# InkTime.net
KiCad netlist of a schematic drawn in EAGLE
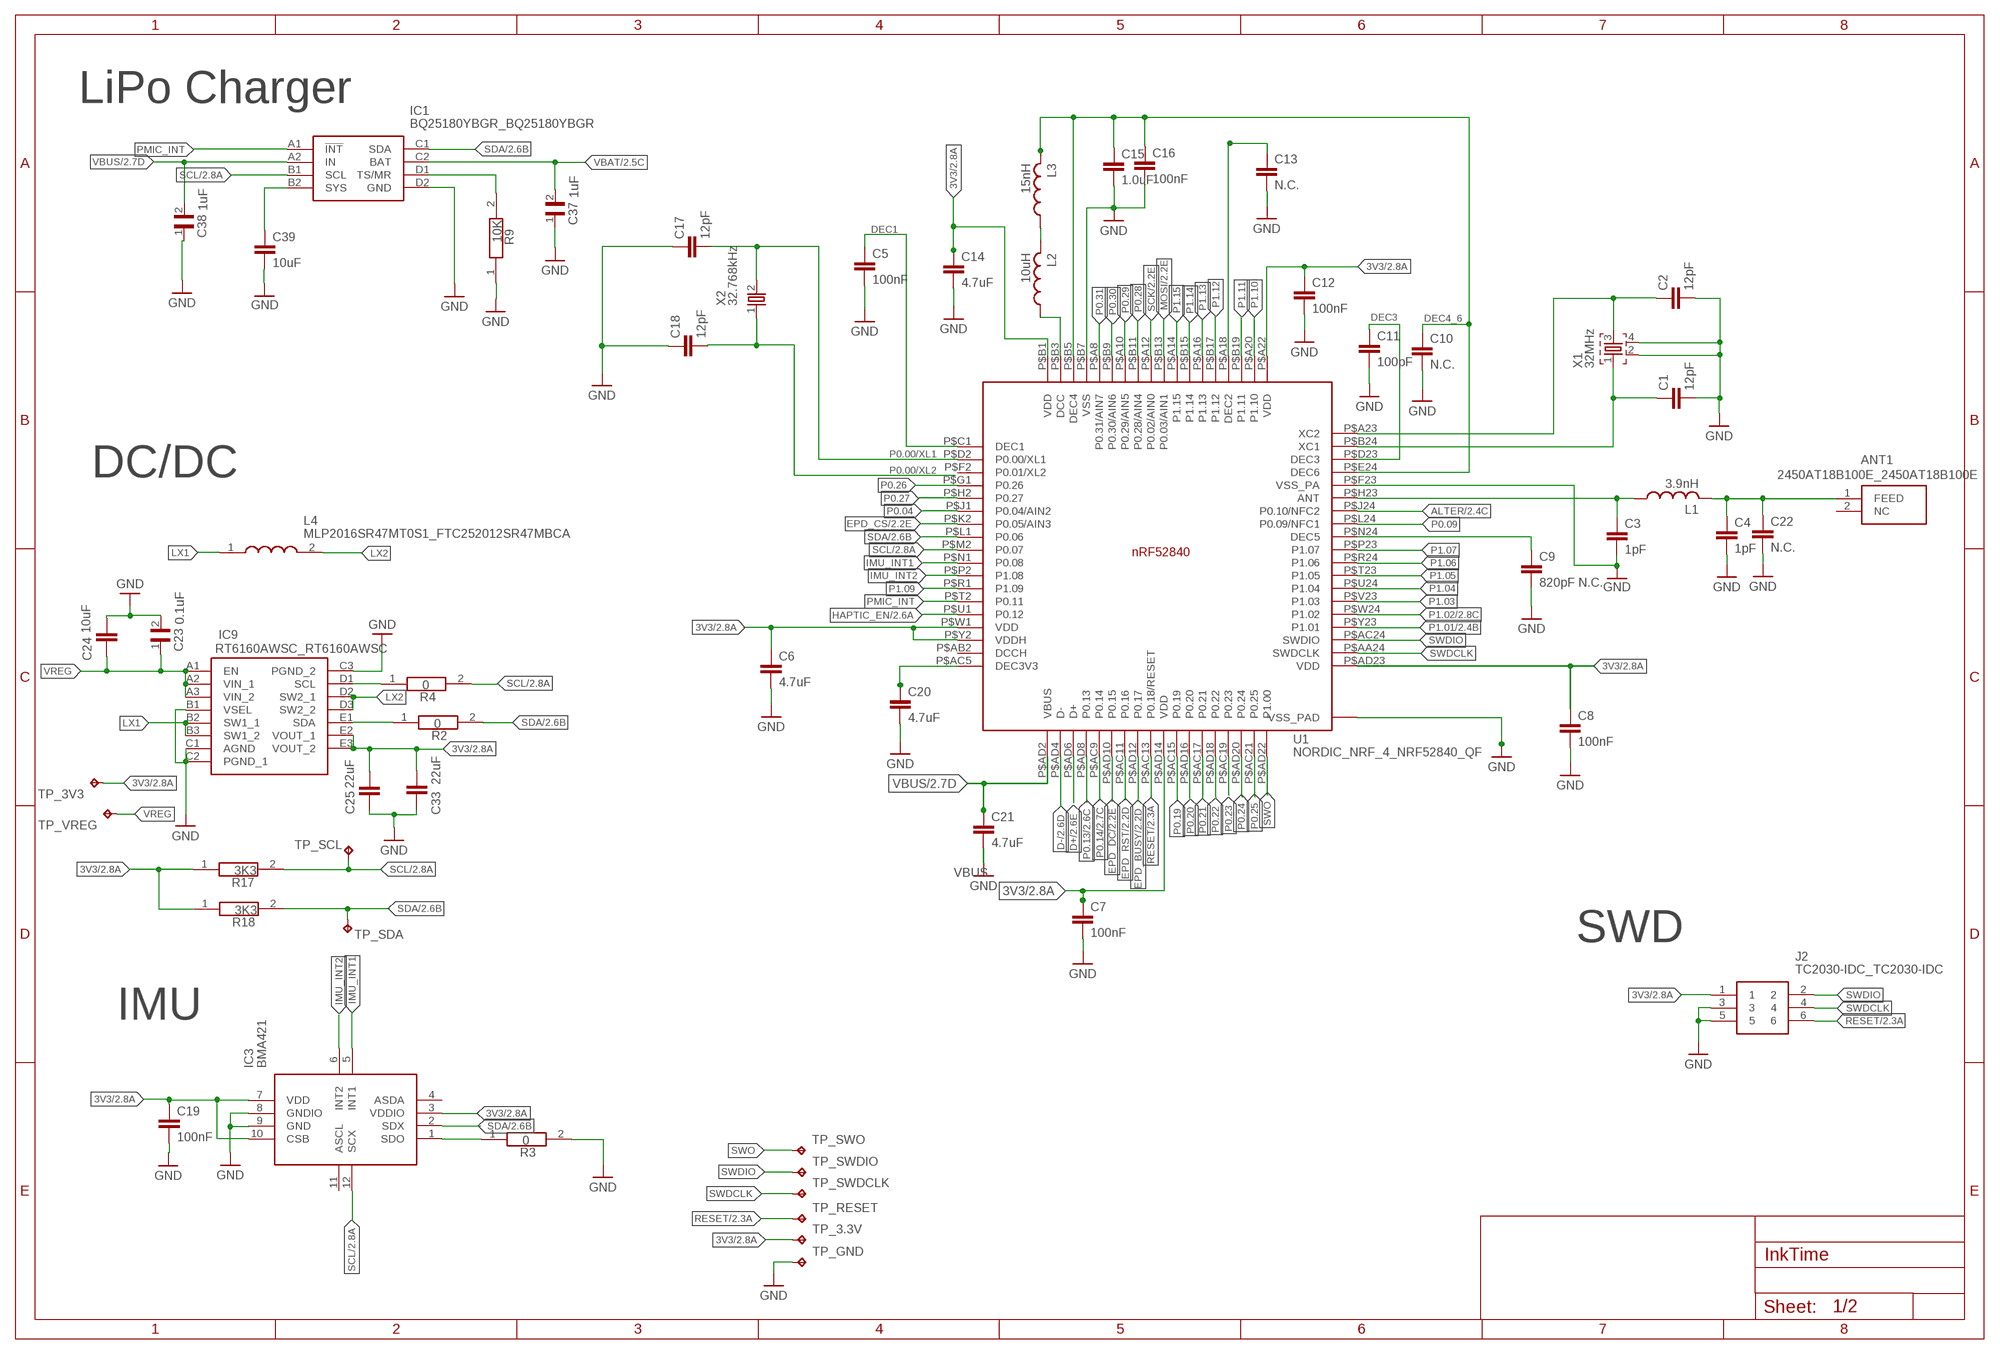
[diagram p0: schematic, sheet 1]
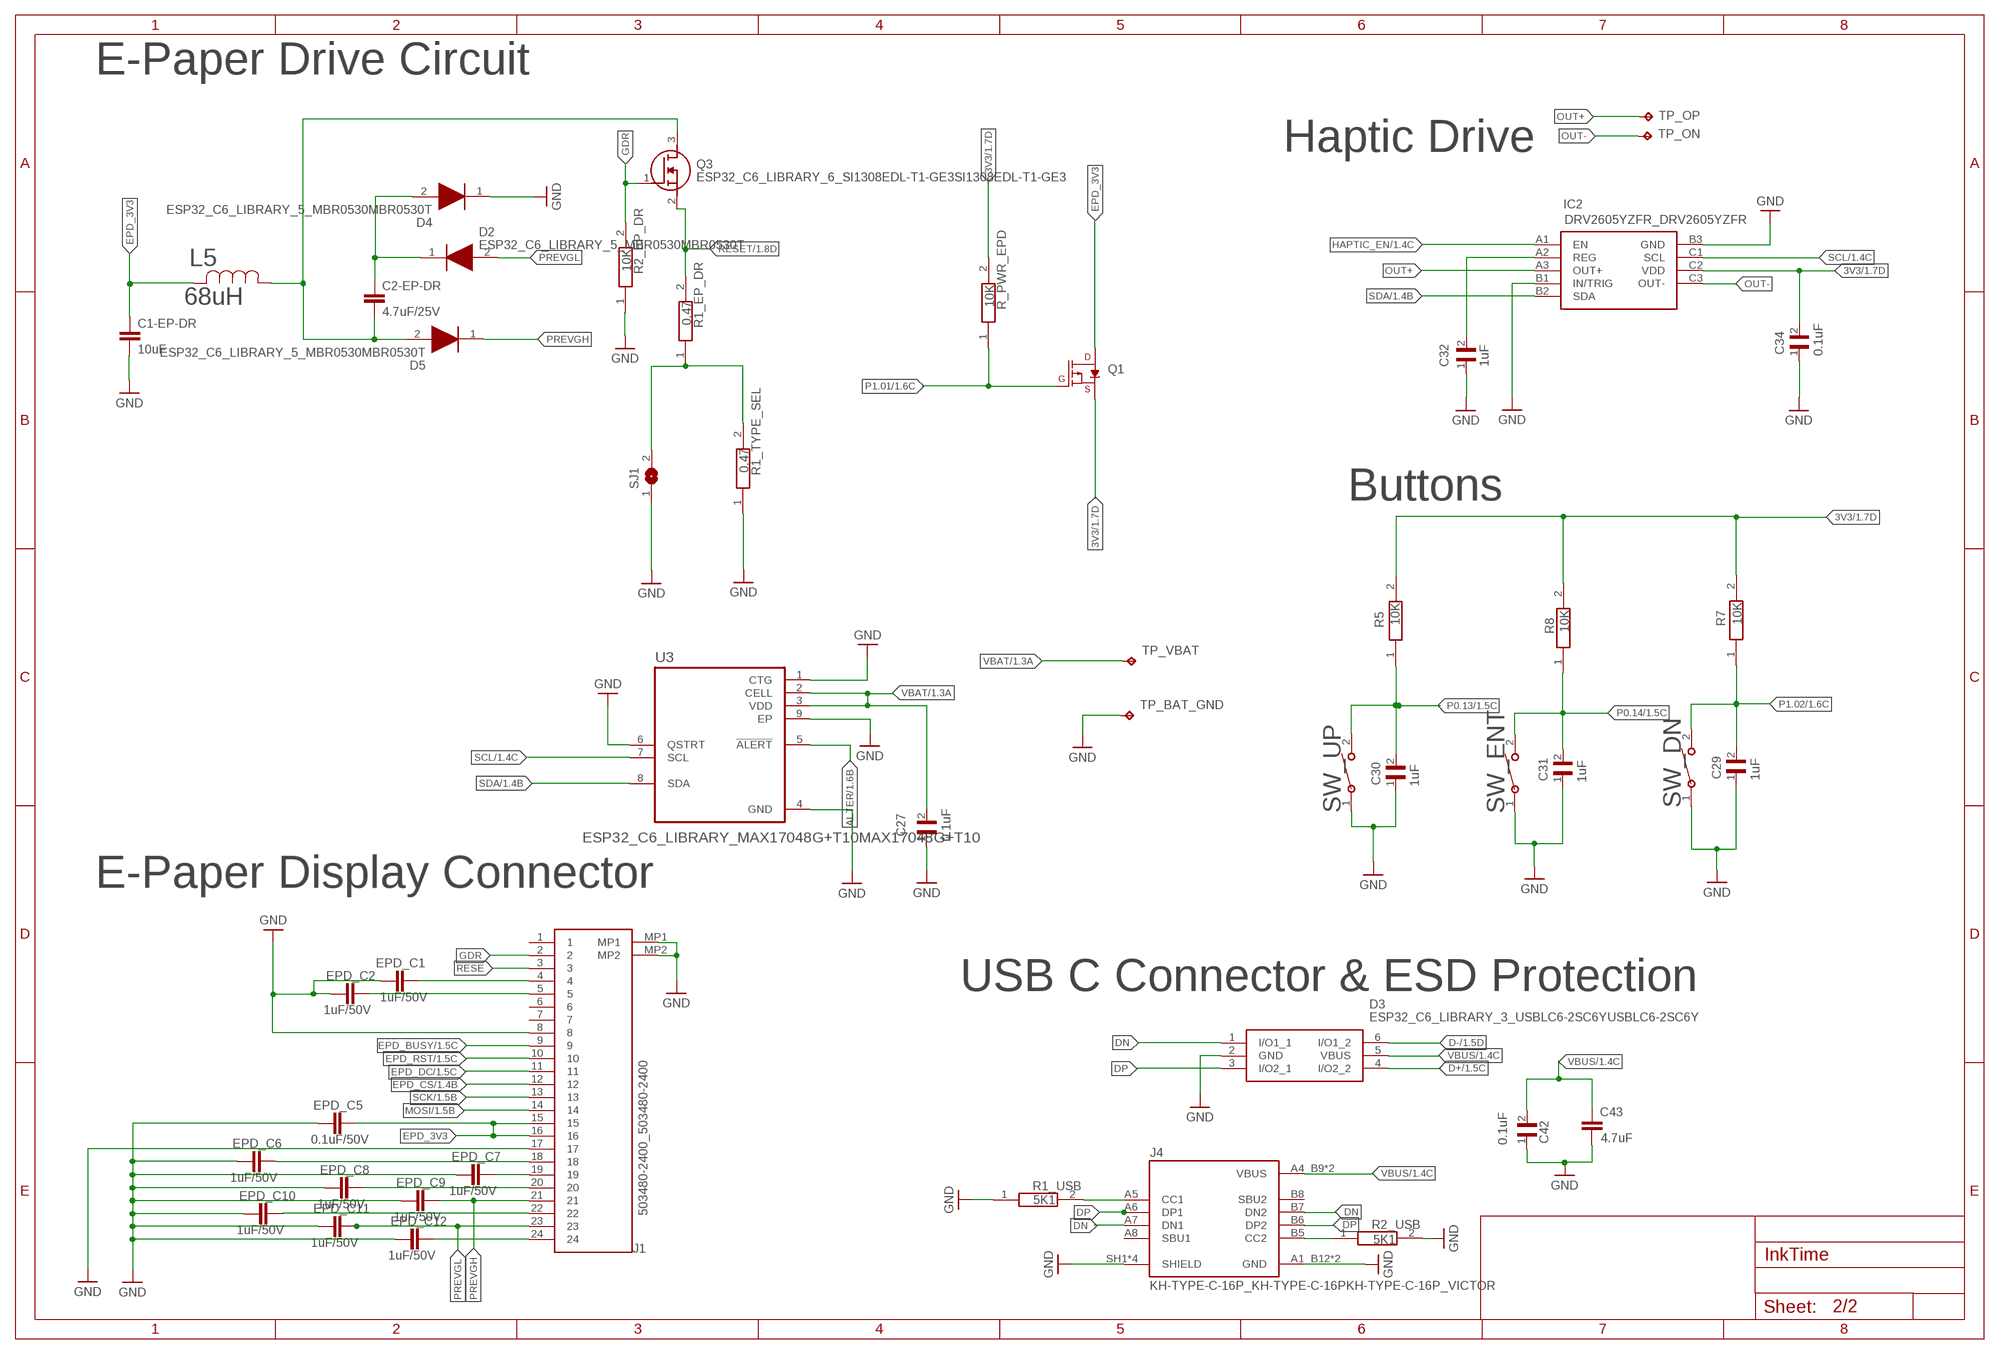
[diagram p1: schematic, sheet 2]

(export (version "E")
  (design (tool "Eeschema 10.0.6"))
  (components
    (comp (ref "ANT1")
      (value "2450AT18B100E_2450AT18B100E")
      (footprint "eagle-import:2450AT18B100E_ANTC3216X140N")
      (fields
        (field (name "ARROW_PART_NUMBER") "2450AT18B100E")
        (field (name "MOUSER_PART_NUMBER") "609-2450AT18B100E")
      )
      (libsource (lib "eagle-import") (part "2450AT18B100E_2450AT18B100E"))
    )
    (comp (ref "C1")
      (value "12pF")
      (footprint "eagle-import:NORDIC_NRF_3_RESC0201_N")
      (libsource (lib "eagle-import") (part "NORDIC_NRF_3_CAPACITOR_0201_N"))
    )
    (comp (ref "C2")
      (value "12pF")
      (footprint "eagle-import:NORDIC_NRF_3_RESC0201_N")
      (libsource (lib "eagle-import") (part "NORDIC_NRF_3_CAPACITOR_0201_N"))
    )
    (comp (ref "C3")
      (value "1pF")
      (footprint "eagle-import:NORDIC_NRF_3_RESC0201_N")
      (libsource (lib "eagle-import") (part "NORDIC_NRF_3_CAPACITOR_0201_N"))
    )
    (comp (ref "C4")
      (value "1pF")
      (footprint "eagle-import:NORDIC_NRF_3_RESC0201_N")
      (libsource (lib "eagle-import") (part "NORDIC_NRF_3_CAPACITOR_0201_N"))
    )
    (comp (ref "C5")
      (value "100nF")
      (footprint "eagle-import:NORDIC_NRF_3_RESC0201_N")
      (libsource (lib "eagle-import") (part "NORDIC_NRF_3_CAPACITOR_0201_N"))
    )
    (comp (ref "C6")
      (value "4.7uF")
      (footprint "eagle-import:NORDIC_NRF_3_RESC0402_N")
      (libsource (lib "eagle-import") (part "NORDIC_NRF_3_CAPACITORCAPACITOR_4020"))
    )
    (comp (ref "C7")
      (value "100nF")
      (footprint "eagle-import:NORDIC_NRF_3_RESC0201_N")
      (libsource (lib "eagle-import") (part "NORDIC_NRF_3_CAPACITOR_0201_N"))
    )
    (comp (ref "C8")
      (value "100nF")
      (footprint "eagle-import:NORDIC_NRF_3_RESC0201_N")
      (libsource (lib "eagle-import") (part "NORDIC_NRF_3_CAPACITOR_0201_N"))
    )
    (comp (ref "C9")
      (value "820pF N.C.")
      (footprint "eagle-import:NORDIC_NRF_3_RESC0201_N")
      (libsource (lib "eagle-import") (part "NORDIC_NRF_3_CAPACITOR_0201_N"))
    )
    (comp (ref "C10")
      (value "N.C.")
      (footprint "eagle-import:NORDIC_NRF_3_RESC0402_N")
      (libsource (lib "eagle-import") (part "NORDIC_NRF_3_CAPACITORCAPACITOR_4020"))
    )
    (comp (ref "C11")
      (value "100pF")
      (footprint "eagle-import:NORDIC_NRF_3_RESC0201_N")
      (libsource (lib "eagle-import") (part "NORDIC_NRF_3_CAPACITOR_0201_N"))
    )
    (comp (ref "C12")
      (value "100nF")
      (footprint "eagle-import:NORDIC_NRF_3_RESC0201_N")
      (libsource (lib "eagle-import") (part "NORDIC_NRF_3_CAPACITOR_0201_N"))
    )
    (comp (ref "C13")
      (value "N.C.")
      (footprint "eagle-import:NORDIC_NRF_3_RESC0201_N")
      (libsource (lib "eagle-import") (part "NORDIC_NRF_3_CAPACITOR_0201_N"))
    )
    (comp (ref "C14")
      (value "4.7uF")
      (footprint "eagle-import:NORDIC_NRF_3_RESC0402_N")
      (libsource (lib "eagle-import") (part "NORDIC_NRF_3_CAPACITORCAPACITOR_4020"))
    )
    (comp (ref "C15")
      (value "1.0uF")
      (footprint "eagle-import:NORDIC_NRF_3_RESC0402_N")
      (libsource (lib "eagle-import") (part "NORDIC_NRF_3_CAPACITORCAPACITOR_4020"))
    )
    (comp (ref "C16")
      (value "100nF")
      (footprint "eagle-import:NORDIC_NRF_3_RESC0201_N")
      (libsource (lib "eagle-import") (part "NORDIC_NRF_3_CAPACITOR_0201_N"))
    )
    (comp (ref "C17")
      (value "12pF")
      (footprint "eagle-import:NORDIC_NRF_3_RESC0201_N")
      (libsource (lib "eagle-import") (part "NORDIC_NRF_3_CAPACITOR_0201_N"))
    )
    (comp (ref "C18")
      (value "12pF")
      (footprint "eagle-import:NORDIC_NRF_3_RESC0201_N")
      (libsource (lib "eagle-import") (part "NORDIC_NRF_3_CAPACITOR_0201_N"))
    )
    (comp (ref "C19")
      (value "100nF")
      (footprint "eagle-import:NORDIC_NRF_3_RESC0201_N")
      (libsource (lib "eagle-import") (part "NORDIC_NRF_3_CAPACITOR_0201_N"))
    )
    (comp (ref "C20")
      (value "4.7uF")
      (footprint "eagle-import:NORDIC_NRF_3_RESC0402_N")
      (libsource (lib "eagle-import") (part "NORDIC_NRF_3_CAPACITORCAPACITOR_4020"))
    )
    (comp (ref "C21")
      (value "4.7uF")
      (footprint "eagle-import:NORDIC_NRF_3_RESC0402_N")
      (libsource (lib "eagle-import") (part "NORDIC_NRF_3_CAPACITORCAPACITOR_4020"))
    )
    (comp (ref "C22")
      (value "N.C.")
      (footprint "eagle-import:NORDIC_NRF_3_RESC0201_N")
      (libsource (lib "eagle-import") (part "NORDIC_NRF_3_CAPACITOR_0201_N"))
    )
    (comp (ref "C23")
      (value "0.1uF")
      (footprint "eagle-import:GRM011R60J152KE01L_2_CAPC0201X13N")
      (libsource (lib "eagle-import") (part "GRM011R60J152KE01L_2_GRM011R60J152KE01LGRM011R60J152KE01L"))
    )
    (comp (ref "C24")
      (value "10uF")
      (footprint "eagle-import:NORDIC_NRF_3_RESC0402_N")
      (libsource (lib "eagle-import") (part "NORDIC_NRF_3_CAPACITORCAPACITOR_4020"))
    )
    (comp (ref "C25")
      (value "22uF")
      (footprint "eagle-import:NORDIC_NRF_3_RESC0402_N")
      (libsource (lib "eagle-import") (part "NORDIC_NRF_3_CAPACITORCAPACITOR_4020"))
    )
    (comp (ref "C33")
      (value "22uF")
      (footprint "eagle-import:NORDIC_NRF_3_RESC0402_N")
      (libsource (lib "eagle-import") (part "NORDIC_NRF_3_CAPACITORCAPACITOR_4020"))
    )
    (comp (ref "C37")
      (value "1uF")
      (footprint "eagle-import:GRM011R60J152KE01L_2_CAPC0201X13N")
      (libsource (lib "eagle-import") (part "GRM011R60J152KE01L_2_GRM011R60J152KE01LGRM011R60J152KE01L"))
    )
    (comp (ref "C38")
      (value "1uF")
      (footprint "eagle-import:GRM011R60J152KE01L_2_CAPC0201X13N")
      (libsource (lib "eagle-import") (part "GRM011R60J152KE01L_2_GRM011R60J152KE01LGRM011R60J152KE01L"))
    )
    (comp (ref "C39")
      (value "10uF")
      (footprint "eagle-import:NORDIC_NRF_3_RESC0402_N")
      (libsource (lib "eagle-import") (part "NORDIC_NRF_3_CAPACITORCAPACITOR_4020"))
    )
    (comp (ref "IC1")
      (value "BQ25180YBGR_BQ25180YBGR")
      (footprint "eagle-import:BQ25180YBGR_BGA8C40P2X4_100X155X50")
      (fields
        (field (name "ARROW_PART_NUMBER") "BQ25180YBGR")
        (field (name "MOUSER_PART_NUMBER") "595-BQ25180YBGR")
      )
      (libsource (lib "eagle-import") (part "BQ25180YBGR_BQ25180YBGR"))
    )
    (comp (ref "IC3")
      (value "BMA421")
      (footprint "eagle-import:BMA423_BMA423")
      (fields (field (name "ARROW_PART_NUMBER") "BMA423") (field (name "MOUSER_PART_NUMBER") "262-BMA423"))
      (libsource (lib "eagle-import") (part "BMA423_BMA423"))
    )
    (comp (ref "IC9")
      (value "RT6160AWSC_RT6160AWSC")
      (footprint "eagle-import:RT6160AWSC_BGA15C40P3X5_140X230X60")
      (fields
        (field (name "MANUFACTURER_PART_NUMBER") "RT6160AWSC")
        (field (name "MOUSER_PART_NUMBER") "835-RT6160AWSC")
      )
      (libsource (lib "eagle-import") (part "RT6160AWSC_RT6160AWSC"))
    )
    (comp (ref "J2")
      (value "TC2030-IDC_TC2030-IDC")
      (footprint "eagle-import:TC2030-IDC_TC2030IDC")
      (fields (field (name "MANUFACTURER_PART_NUMBER") "TC2030-IDC"))
      (libsource (lib "eagle-import") (part "TC2030-IDC_TC2030-IDC"))
    )
    (comp (ref "L1")
      (value "3.9nH")
      (footprint "eagle-import:NORDIC_NRF_2_RESC0201_N")
      (libsource (lib "eagle-import") (part "NORDIC_NRF_2_INDUCTOR_0201_N"))
    )
    (comp (ref "L2")
      (value "10uH")
      (footprint "eagle-import:NORDIC_NRF_2_RESC0402_N")
      (libsource (lib "eagle-import") (part "NORDIC_NRF_2_INDUCTOR_0402_N"))
    )
    (comp (ref "L3")
      (value "15nH")
      (footprint "eagle-import:NORDIC_NRF_2_RESC0201_N")
      (libsource (lib "eagle-import") (part "NORDIC_NRF_2_INDUCTOR_0201_N"))
    )
    (comp (ref "L4")
      (value "MLP2016SR47MT0S1_FTC252012SR47MBCA")
      (footprint "eagle-import:MLP2016SR47MT0S1_INDC2016X100N")
      (fields (field (name "MANUFACTURER_PART_NUMBER") "FTC252012SR47MBCA"))
      (libsource (lib "eagle-import") (part "MLP2016SR47MT0S1_FTC252012SR47MBCA"))
    )
    (comp (ref "R2")
      (value "0")
      (footprint "eagle-import:CPF0201D7K68C1_0201")
      (libsource (lib "eagle-import") (part "CPF0201D7K68C1_CPF0201D7K68C1"))
    )
    (comp (ref "R3")
      (value "0")
      (footprint "eagle-import:CPF0201D7K68C1_0201")
      (libsource (lib "eagle-import") (part "CPF0201D7K68C1_CPF0201D7K68C1"))
    )
    (comp (ref "R4")
      (value "0")
      (footprint "eagle-import:CPF0201D7K68C1_0201")
      (libsource (lib "eagle-import") (part "CPF0201D7K68C1_CPF0201D7K68C1"))
    )
    (comp (ref "R9")
      (value "10K")
      (footprint "eagle-import:CPF0201D7K68C1_0201")
      (libsource (lib "eagle-import") (part "CPF0201D7K68C1_CPF0201D7K68C1"))
    )
    (comp (ref "R17")
      (value "3K3")
      (footprint "eagle-import:CPF0201D7K68C1_0201")
      (libsource (lib "eagle-import") (part "CPF0201D7K68C1_CPF0201D7K68C1"))
    )
    (comp (ref "R18")
      (value "3K3")
      (footprint "eagle-import:CPF0201D7K68C1_0201")
      (libsource (lib "eagle-import") (part "CPF0201D7K68C1_CPF0201D7K68C1"))
    )
    (comp (ref "TP_3.3V")
      (value "HECTOR_WATCH_1_TPTP20R")
      (footprint "eagle-import:HECTOR_WATCH_1_TP20R")
      (libsource (lib "eagle-import") (part "HECTOR_WATCH_1_TPTP20R"))
    )
    (comp (ref "TP_3V3")
      (value "HECTOR_WATCH_1_TPTP20R")
      (footprint "eagle-import:HECTOR_WATCH_1_TP20R")
      (libsource (lib "eagle-import") (part "HECTOR_WATCH_1_TPTP20R"))
    )
    (comp (ref "TP_GND")
      (value "HECTOR_WATCH_1_TPTP20R")
      (footprint "eagle-import:HECTOR_WATCH_1_TP20R")
      (libsource (lib "eagle-import") (part "HECTOR_WATCH_1_TPTP20R"))
    )
    (comp (ref "TP_RESET")
      (value "HECTOR_WATCH_1_TPTP20R")
      (footprint "eagle-import:HECTOR_WATCH_1_TP20R")
      (libsource (lib "eagle-import") (part "HECTOR_WATCH_1_TPTP20R"))
    )
    (comp (ref "TP_SCL")
      (value "HECTOR_WATCH_1_TPTP20R")
      (footprint "eagle-import:HECTOR_WATCH_1_TP20R")
      (libsource (lib "eagle-import") (part "HECTOR_WATCH_1_TPTP20R"))
    )
    (comp (ref "TP_SDA")
      (value "HECTOR_WATCH_1_TPTP20R")
      (footprint "eagle-import:HECTOR_WATCH_1_TP20R")
      (libsource (lib "eagle-import") (part "HECTOR_WATCH_1_TPTP20R"))
    )
    (comp (ref "TP_SWDCLK")
      (value "HECTOR_WATCH_1_TPTP20R")
      (footprint "eagle-import:HECTOR_WATCH_1_TP20R")
      (libsource (lib "eagle-import") (part "HECTOR_WATCH_1_TPTP20R"))
    )
    (comp (ref "TP_SWDIO")
      (value "HECTOR_WATCH_1_TPTP20R")
      (footprint "eagle-import:HECTOR_WATCH_1_TP20R")
      (libsource (lib "eagle-import") (part "HECTOR_WATCH_1_TPTP20R"))
    )
    (comp (ref "TP_SWO")
      (value "HECTOR_WATCH_1_TPTP20R")
      (footprint "eagle-import:HECTOR_WATCH_1_TP20R")
      (libsource (lib "eagle-import") (part "HECTOR_WATCH_1_TPTP20R"))
    )
    (comp (ref "TP_VREG")
      (value "HECTOR_WATCH_1_TPTP20R")
      (footprint "eagle-import:HECTOR_WATCH_1_TP20R")
      (libsource (lib "eagle-import") (part "HECTOR_WATCH_1_TPTP20R"))
    )
    (comp (ref "U1")
      (value "NORDIC_NRF_4_NRF52840_QF")
      (footprint "eagle-import:NORDIC_NRF_4_AQFN50P700X700X85_HS-74N")
      (libsource (lib "eagle-import") (part "NORDIC_NRF_4_NRF52840_QF"))
    )
    (comp (ref "X1")
      (value "32MHz")
      (footprint "eagle-import:NORDIC_NRF_BT-XTAL_2016_N")
      (libsource (lib "eagle-import") (part "NORDIC_NRF_XTAL_32MHZ"))
    )
    (comp (ref "X2")
      (value "32.768kHz")
      (footprint "eagle-import:NORDIC_NRF_1_XTAL_3215_N")
      (libsource (lib "eagle-import") (part "NORDIC_NRF_1_XTAL_32KHZ"))
    )
    (comp (ref "C1-EP-DR")
      (value "10uF")
      (footprint "eagle-import:NORDIC_NRF_3_RESC0402_N")
      (libsource (lib "eagle-import") (part "NORDIC_NRF_3_CAPACITORCAPACITOR_4020"))
    )
    (comp (ref "C2-EP-DR")
      (value "4.7uF/25V")
      (footprint "eagle-import:NORDIC_NRF_3_RESC0201_N")
      (libsource (lib "eagle-import") (part "NORDIC_NRF_3_CAPACITOR_0201_N"))
    )
    (comp (ref "C27")
      (value "0.1uF")
      (footprint "eagle-import:GRM011R60J152KE01L_2_CAPC0201X13N")
      (libsource (lib "eagle-import") (part "GRM011R60J152KE01L_2_GRM011R60J152KE01LGRM011R60J152KE01L"))
    )
    (comp (ref "C29")
      (value "1uF")
      (footprint "eagle-import:GRM011R60J152KE01L_2_CAPC0201X13N")
      (libsource (lib "eagle-import") (part "GRM011R60J152KE01L_2_GRM011R60J152KE01LGRM011R60J152KE01L"))
    )
    (comp (ref "C30")
      (value "1uF")
      (footprint "eagle-import:GRM011R60J152KE01L_2_CAPC0201X13N")
      (libsource (lib "eagle-import") (part "GRM011R60J152KE01L_2_GRM011R60J152KE01LGRM011R60J152KE01L"))
    )
    (comp (ref "C31")
      (value "1uF")
      (footprint "eagle-import:GRM011R60J152KE01L_2_CAPC0201X13N")
      (libsource (lib "eagle-import") (part "GRM011R60J152KE01L_2_GRM011R60J152KE01LGRM011R60J152KE01L"))
    )
    (comp (ref "C32")
      (value "1uF")
      (footprint "eagle-import:GRM011R60J152KE01L_2_CAPC0201X13N")
      (libsource (lib "eagle-import") (part "GRM011R60J152KE01L_2_GRM011R60J152KE01LGRM011R60J152KE01L"))
    )
    (comp (ref "C34")
      (value "0.1uF")
      (footprint "eagle-import:GRM011R60J152KE01L_2_CAPC0201X13N")
      (libsource (lib "eagle-import") (part "GRM011R60J152KE01L_2_GRM011R60J152KE01LGRM011R60J152KE01L"))
    )
    (comp (ref "C42")
      (value "0.1uF")
      (footprint "eagle-import:GRM011R60J152KE01L_2_CAPC0201X13N")
      (libsource (lib "eagle-import") (part "GRM011R60J152KE01L_2_GRM011R60J152KE01LGRM011R60J152KE01L"))
    )
    (comp (ref "C43")
      (value "4.7uF")
      (footprint "eagle-import:NORDIC_NRF_3_RESC0402_N")
      (libsource (lib "eagle-import") (part "NORDIC_NRF_3_CAPACITORCAPACITOR_4020"))
    )
    (comp (ref "D2")
      (value "ESP32_C6_LIBRARY_5_MBR0530MBR0530T")
      (footprint "eagle-import:ESP32_C6_LIBRARY_5_SOD3716X135N")
      (libsource (lib "eagle-import") (part "ESP32_C6_LIBRARY_5_MBR0530MBR0530T"))
    )
    (comp (ref "D3")
      (value "ESP32_C6_LIBRARY_3_USBLC6-2SC6YUSBLC6-2SC6Y")
      (footprint "eagle-import:ESP32_C6_LIBRARY_3_SOT95P280X145-6N")
      (libsource (lib "eagle-import") (part "ESP32_C6_LIBRARY_3_USBLC6-2SC6YUSBLC6-2SC6Y"))
    )
    (comp (ref "D4")
      (value "ESP32_C6_LIBRARY_5_MBR0530MBR0530T")
      (footprint "eagle-import:ESP32_C6_LIBRARY_5_SOD3716X135N")
      (libsource (lib "eagle-import") (part "ESP32_C6_LIBRARY_5_MBR0530MBR0530T"))
    )
    (comp (ref "D5")
      (value "ESP32_C6_LIBRARY_5_MBR0530MBR0530T")
      (footprint "eagle-import:ESP32_C6_LIBRARY_5_SOD3716X135N")
      (libsource (lib "eagle-import") (part "ESP32_C6_LIBRARY_5_MBR0530MBR0530T"))
    )
    (comp (ref "EPD_C1")
      (value "1uF/50V")
      (footprint "eagle-import:NORDIC_NRF_3_RESC0402_N")
      (libsource (lib "eagle-import") (part "NORDIC_NRF_3_CAPACITORCAPACITOR_4020"))
    )
    (comp (ref "EPD_C2")
      (value "1uF/50V")
      (footprint "eagle-import:NORDIC_NRF_3_RESC0402_N")
      (libsource (lib "eagle-import") (part "NORDIC_NRF_3_CAPACITORCAPACITOR_4020"))
    )
    (comp (ref "EPD_C5")
      (value "0.1uF/50V")
      (footprint "eagle-import:NORDIC_NRF_3_RESC0402_N")
      (libsource (lib "eagle-import") (part "NORDIC_NRF_3_CAPACITORCAPACITOR_4020"))
    )
    (comp (ref "EPD_C6")
      (value "1uF/50V")
      (footprint "eagle-import:NORDIC_NRF_3_RESC0402_N")
      (libsource (lib "eagle-import") (part "NORDIC_NRF_3_CAPACITORCAPACITOR_4020"))
    )
    (comp (ref "EPD_C7")
      (value "1uF/50V")
      (footprint "eagle-import:NORDIC_NRF_3_RESC0402_N")
      (libsource (lib "eagle-import") (part "NORDIC_NRF_3_CAPACITORCAPACITOR_4020"))
    )
    (comp (ref "EPD_C8")
      (value "1uF/50V")
      (footprint "eagle-import:NORDIC_NRF_3_RESC0402_N")
      (libsource (lib "eagle-import") (part "NORDIC_NRF_3_CAPACITORCAPACITOR_4020"))
    )
    (comp (ref "EPD_C9")
      (value "1uF/50V")
      (footprint "eagle-import:NORDIC_NRF_3_RESC0402_N")
      (libsource (lib "eagle-import") (part "NORDIC_NRF_3_CAPACITORCAPACITOR_4020"))
    )
    (comp (ref "EPD_C10")
      (value "1uF/50V")
      (footprint "eagle-import:NORDIC_NRF_3_RESC0402_N")
      (libsource (lib "eagle-import") (part "NORDIC_NRF_3_CAPACITORCAPACITOR_4020"))
    )
    (comp (ref "EPD_C11")
      (value "1uF/50V")
      (footprint "eagle-import:NORDIC_NRF_3_RESC0402_N")
      (libsource (lib "eagle-import") (part "NORDIC_NRF_3_CAPACITORCAPACITOR_4020"))
    )
    (comp (ref "EPD_C12")
      (value "1uF/50V")
      (footprint "eagle-import:NORDIC_NRF_3_RESC0402_N")
      (libsource (lib "eagle-import") (part "NORDIC_NRF_3_CAPACITORCAPACITOR_4020"))
    )
    (comp (ref "IC2")
      (value "DRV2605YZFR_DRV2605YZFR")
      (footprint "eagle-import:DRV2605YZFR_BGA9C50P3X3_144X144X62")
      (fields (field (name "ARROW_PART_NUMBER") "DRV2605YZFR"))
      (libsource (lib "eagle-import") (part "DRV2605YZFR_DRV2605YZFR"))
    )
    (comp (ref "J1")
      (value "503480-2400_503480-2400")
      (footprint "eagle-import:503480-2400_5034802400")
      (fields
        (field (name "MANUFACTURER_PART_NUMBER") "503480-2400")
        (field (name "MOUSER_PART_NUMBER") "538-503480-2400")
      )
      (libsource (lib "eagle-import") (part "503480-2400_503480-2400"))
    )
    (comp (ref "J4")
      (value "KH-TYPE-C-16P_KH-TYPE-C-16PKH-TYPE-C-16P_VICTOR")
      (footprint "eagle-import:KH-TYPE-C-16P_KINGHELM_KH-TYPE-C-16P")
      (libsource (lib "eagle-import") (part "KH-TYPE-C-16P_KH-TYPE-C-16PKH-TYPE-C-16P_VICTOR"))
    )
    (comp (ref "L5")
      (value "68uH")
      (footprint "eagle-import:ESP32_C6_LIBRARY_2_IND_4828-WE-TPC_WRE")
      (fields
        (field (name "MANUFACTURER_PART_NUMBER") "744043680")
        (field (name "COPYRIGHT") "Copyright (C) 2024 Ultra Librarian. All rights reserved.")
      )
      (libsource (lib "eagle-import") (part "ESP32_C6_LIBRARY_2_744043680IND_4828-WE-TPC_WRE"))
    )
    (comp (ref "Q1")
      (value "ESP32_C6_LIBRARY_4_ESP32_WROVER_SPARKFUN-DISCRETESEMI_MOSFET_PCH")
      (footprint "eagle-import:ESP32_C6_LIBRARY_4_ESP32_C6_LIBRARY_4_ESP32_C6_LIBRARY_4_ESP32_C6_LIBRARY_4_ESP32_WROVER_SPARKFUN-DISCRETESEMI_SOT23-3")
      (libsource (lib "eagle-import") (part "ESP32_C6_LIBRARY_4_ESP32_WROVER_SPARKFUN-DISCRETESEMI_MOSFET_PCH"))
    )
    (comp (ref "Q3")
      (value "ESP32_C6_LIBRARY_6_SI1308EDL-T1-GE3SI1308EDL-T1-GE3")
      (footprint "eagle-import:ESP32_C6_LIBRARY_6_SOT65P210X110-3N")
      (libsource (lib "eagle-import") (part "ESP32_C6_LIBRARY_6_SI1308EDL-T1-GE3SI1308EDL-T1-GE3"))
    )
    (comp (ref "R1_EP_DR")
      (value "0.47")
      (footprint "eagle-import:CPF0201D7K68C1_0201")
      (libsource (lib "eagle-import") (part "CPF0201D7K68C1_CPF0201D7K68C1"))
    )
    (comp (ref "R1_TYPE_SEL")
      (value "0.47")
      (footprint "eagle-import:CPF0201D7K68C1_0201")
      (libsource (lib "eagle-import") (part "CPF0201D7K68C1_CPF0201D7K68C1"))
    )
    (comp (ref "R1_USB")
      (value "5K1")
      (footprint "eagle-import:CPF0201D7K68C1_0201")
      (libsource (lib "eagle-import") (part "CPF0201D7K68C1_CPF0201D7K68C1"))
    )
    (comp (ref "R2_EP_DR")
      (value "10K")
      (footprint "eagle-import:CPF0201D7K68C1_0201")
      (libsource (lib "eagle-import") (part "CPF0201D7K68C1_CPF0201D7K68C1"))
    )
    (comp (ref "R2_USB")
      (value "5K1")
      (footprint "eagle-import:CPF0201D7K68C1_0201")
      (libsource (lib "eagle-import") (part "CPF0201D7K68C1_CPF0201D7K68C1"))
    )
    (comp (ref "R5")
      (value "10K")
      (footprint "eagle-import:CPF0201D7K68C1_0201")
      (libsource (lib "eagle-import") (part "CPF0201D7K68C1_CPF0201D7K68C1"))
    )
    (comp (ref "R7")
      (value "10K")
      (footprint "eagle-import:CPF0201D7K68C1_0201")
      (libsource (lib "eagle-import") (part "CPF0201D7K68C1_CPF0201D7K68C1"))
    )
    (comp (ref "R8")
      (value "10K")
      (footprint "eagle-import:CPF0201D7K68C1_0201")
      (libsource (lib "eagle-import") (part "CPF0201D7K68C1_CPF0201D7K68C1"))
    )
    (comp (ref "R_PWR_EPD")
      (value "10K")
      (footprint "eagle-import:CPF0201D7K68C1_0201")
      (libsource (lib "eagle-import") (part "CPF0201D7K68C1_CPF0201D7K68C1"))
    )
    (comp (ref "SJ1")
      (value "ESP32_C6_LIBRARY_7_JUMPER_SJ")
      (footprint "eagle-import:ESP32_C6_LIBRARY_7_JUMPER_SJ")
      (libsource (lib "eagle-import") (part "ESP32_C6_LIBRARY_7_JUMPER_SJ"))
    )
    (comp (ref "SW_DN")
      (value "2025-10-22_07-23-44_LIBRARY_EVP-AKE31A")
      (footprint "eagle-import:2025-10-22_07-23-44_LIBRARY_SW_EVP-AKE31A_PAN")
      (libsource (lib "eagle-import") (part "2025-10-22_07-23-44_LIBRARY_EVP-AKE31A"))
    )
    (comp (ref "SW_ENT")
      (value "2025-10-22_07-23-44_LIBRARY_EVP-AKE31A")
      (footprint "eagle-import:2025-10-22_07-23-44_LIBRARY_SW_EVP-AKE31A_PAN")
      (libsource (lib "eagle-import") (part "2025-10-22_07-23-44_LIBRARY_EVP-AKE31A"))
    )
    (comp (ref "SW_UP")
      (value "2025-10-22_07-23-44_LIBRARY_EVP-AKE31A")
      (footprint "eagle-import:2025-10-22_07-23-44_LIBRARY_SW_EVP-AKE31A_PAN")
      (libsource (lib "eagle-import") (part "2025-10-22_07-23-44_LIBRARY_EVP-AKE31A"))
    )
    (comp (ref "TP_BAT_GND")
      (value "HECTOR_WATCH_1_TPTP20R")
      (footprint "eagle-import:HECTOR_WATCH_1_TP20R")
      (libsource (lib "eagle-import") (part "HECTOR_WATCH_1_TPTP20R"))
    )
    (comp (ref "TP_ON")
      (value "HECTOR_WATCH_1_TPTP20R")
      (footprint "eagle-import:HECTOR_WATCH_1_TP20R")
      (libsource (lib "eagle-import") (part "HECTOR_WATCH_1_TPTP20R"))
    )
    (comp (ref "TP_OP")
      (value "HECTOR_WATCH_1_TPTP20R")
      (footprint "eagle-import:HECTOR_WATCH_1_TP20R")
      (libsource (lib "eagle-import") (part "HECTOR_WATCH_1_TPTP20R"))
    )
    (comp (ref "TP_VBAT")
      (value "HECTOR_WATCH_1_TPTP20R")
      (footprint "eagle-import:HECTOR_WATCH_1_TP20R")
      (libsource (lib "eagle-import") (part "HECTOR_WATCH_1_TPTP20R"))
    )
    (comp (ref "U3")
      (value "ESP32_C6_LIBRARY_MAX17048G+T10MAX17048G+T10")
      (footprint "eagle-import:ESP32_C6_LIBRARY_SON50P200X200X80-9N")
      (libsource (lib "eagle-import") (part "ESP32_C6_LIBRARY_MAX17048G+T10MAX17048G+T10"))
    )
  )
  (nets
    (net (code "1") (name "3V3") (class "Default")
      (node (ref "C12") (pin "1") (pinfunction "1_1") (pintype "passive"))
      (node (ref "C14") (pin "1") (pinfunction "1_1") (pintype "passive"))
      (node (ref "C19") (pin "1") (pinfunction "1_1") (pintype "passive"))
      (node (ref "C25") (pin "1") (pinfunction "1_1") (pintype "passive"))
      (node (ref "C33") (pin "1") (pinfunction "1_1") (pintype "passive"))
      (node (ref "C34") (pin "2") (pinfunction "2_2") (pintype "passive"))
      (node (ref "C6") (pin "1") (pinfunction "1_1") (pintype "passive"))
      (node (ref "C7") (pin "1") (pinfunction "1_1") (pintype "passive"))
      (node (ref "C8") (pin "1") (pinfunction "1_1") (pintype "passive"))
      (node (ref "IC2") (pin "C2") (pinfunction "VDD_C2") (pintype "bidirectional"))
      (node (ref "IC3") (pin "10") (pinfunction "CSB_10") (pintype "bidirectional"))
      (node (ref "IC3") (pin "3") (pinfunction "VDDIO_3") (pintype "bidirectional"))
      (node (ref "IC3") (pin "7") (pinfunction "VDD_7") (pintype "bidirectional"))
      (node (ref "IC9") (pin "E2") (pinfunction "VOUT_1_E2") (pintype "bidirectional"))
      (node (ref "IC9") (pin "E3") (pinfunction "VOUT_2_E3") (pintype "bidirectional"))
      (node (ref "J2") (pin "1") (pinfunction "1_1") (pintype "bidirectional"))
      (node (ref "Q1") (pin "2") (pinfunction "S_2") (pintype "bidirectional"))
      (node (ref "R17") (pin "1") (pinfunction "1_1") (pintype "bidirectional"))
      (node (ref "R18") (pin "1") (pinfunction "1_1") (pintype "bidirectional"))
      (node (ref "R5") (pin "2") (pinfunction "2_2") (pintype "bidirectional"))
      (node (ref "R7") (pin "2") (pinfunction "2_2") (pintype "bidirectional"))
      (node (ref "R8") (pin "2") (pinfunction "2_2") (pintype "bidirectional"))
      (node (ref "R_PWR_EPD") (pin "2") (pinfunction "2_2") (pintype "bidirectional"))
      (node (ref "TP_3.3V") (pin "TP") (pinfunction "TP_TP") (pintype "input"))
      (node (ref "TP_3V3") (pin "TP") (pinfunction "TP_TP") (pintype "input"))
      (node (ref "U1") (pin "P$A22") (pinfunction "VDD_P$A22") (pintype "power_in"))
      (node (ref "U1") (pin "P$AD14") (pinfunction "VDD_P$AD14") (pintype "power_in"))
      (node (ref "U1") (pin "P$AD23") (pinfunction "VDD_P$AD23") (pintype "power_in"))
      (node (ref "U1") (pin "P$B1") (pinfunction "VDD_P$B1") (pintype "power_in"))
      (node (ref "U1") (pin "P$W1") (pinfunction "VDD_P$W1") (pintype "power_in"))
    )
    (net (code "2") (name "ALTER") (class "Default")
      (node (ref "U1") (pin "P$J24") (pinfunction "P0.10/NFC2_P$J24") (pintype "bidirectional"))
      (node (ref "U3") (pin "5") (pinfunction "~{ALERT}_5") (pintype "output"))
    )
    (net (code "3") (name "D+") (class "Default")
      (node (ref "D3") (pin "4") (pinfunction "I/O2_2_4") (pintype "bidirectional"))
      (node (ref "U1") (pin "P$AD6") (pinfunction "D+_P$AD6") (pintype "bidirectional"))
    )
    (net (code "4") (name "D-") (class "Default")
      (node (ref "D3") (pin "6") (pinfunction "I/O1_2_6") (pintype "bidirectional"))
      (node (ref "U1") (pin "P$AD4") (pinfunction "D-_P$AD4") (pintype "bidirectional"))
    )
    (net (code "5") (name "DEC1") (class "Default")
      (node (ref "C5") (pin "1") (pinfunction "1_1") (pintype "passive"))
      (node (ref "U1") (pin "P$C1") (pinfunction "DEC1_P$C1") (pintype "power_in"))
    )
    (net (code "6") (name "DEC3") (class "Default")
      (node (ref "C11") (pin "1") (pinfunction "1_1") (pintype "passive"))
      (node (ref "U1") (pin "P$D23") (pinfunction "DEC3_P$D23") (pintype "bidirectional"))
    )
    (net (code "7") (name "DEC4_6") (class "Default")
      (node (ref "C10") (pin "1") (pinfunction "1_1") (pintype "passive"))
      (node (ref "C15") (pin "1") (pinfunction "1_1") (pintype "passive"))
      (node (ref "C16") (pin "1") (pinfunction "1_1") (pintype "passive"))
      (node (ref "L3") (pin "2") (pinfunction "2_2") (pintype "passive"))
      (node (ref "U1") (pin "P$B5") (pinfunction "DEC4_P$B5") (pintype "power_in"))
      (node (ref "U1") (pin "P$E24") (pinfunction "DEC6_P$E24") (pintype "bidirectional"))
    )
    (net (code "8") (name "DN") (class "Default")
      (node (ref "D3") (pin "1") (pinfunction "I/O1_1_1") (pintype "bidirectional"))
      (node (ref "J4") (pin "A7") (pinfunction "DN1_A7") (pintype "bidirectional"))
      (node (ref "J4") (pin "B7") (pinfunction "DN2_B7") (pintype "bidirectional"))
    )
    (net (code "9") (name "DP") (class "Default")
      (node (ref "D3") (pin "3") (pinfunction "I/O2_1_3") (pintype "bidirectional"))
      (node (ref "J4") (pin "A6") (pinfunction "DP1_A6") (pintype "bidirectional"))
      (node (ref "J4") (pin "B6") (pinfunction "DP2_B6") (pintype "bidirectional"))
    )
    (net (code "10") (name "EPD_3V3") (class "Default")
      (node (ref "C1-EP-DR") (pin "1") (pinfunction "1_1") (pintype "passive"))
      (node (ref "EPD_C5") (pin "1") (pinfunction "1_1") (pintype "passive"))
      (node (ref "J1") (pin "15") (pinfunction "15_15") (pintype "bidirectional"))
      (node (ref "J1") (pin "16") (pinfunction "16_16") (pintype "bidirectional"))
      (node (ref "L5") (pin "2") (pinfunction "2_2") (pintype "passive"))
      (node (ref "Q1") (pin "3") (pinfunction "D_3") (pintype "bidirectional"))
    )
    (net (code "11") (name "EPD_BUSY") (class "Default")
      (node (ref "J1") (pin "9") (pinfunction "9_9") (pintype "bidirectional"))
      (node (ref "U1") (pin "P$AD12") (pinfunction "P0.17_P$AD12") (pintype "bidirectional"))
    )
    (net (code "12") (name "EPD_CS") (class "Default")
      (node (ref "J1") (pin "12") (pinfunction "12_12") (pintype "bidirectional"))
      (node (ref "U1") (pin "P$K2") (pinfunction "P0.05/AIN3_P$K2") (pintype "bidirectional"))
    )
    (net (code "13") (name "EPD_DC") (class "Default")
      (node (ref "J1") (pin "11") (pinfunction "11_11") (pintype "bidirectional"))
      (node (ref "U1") (pin "P$AD10") (pinfunction "P0.15_P$AD10") (pintype "bidirectional"))
    )
    (net (code "14") (name "EPD_RST") (class "Default")
      (node (ref "J1") (pin "10") (pinfunction "10_10") (pintype "bidirectional"))
      (node (ref "U1") (pin "P$AC11") (pinfunction "P0.16_P$AC11") (pintype "bidirectional"))
    )
    (net (code "15") (name "GDR") (class "Default")
      (node (ref "J1") (pin "2") (pinfunction "2_2") (pintype "bidirectional"))
      (node (ref "Q3") (pin "1") (pinfunction "G_1") (pintype "bidirectional"))
      (node (ref "R2_EP_DR") (pin "2") (pinfunction "2_2") (pintype "bidirectional"))
    )
    (net (code "16") (name "GND") (class "Default")
      (node (ref "C1") (pin "2") (pinfunction "2_2") (pintype "passive"))
      (node (ref "C1-EP-DR") (pin "2") (pinfunction "2_2") (pintype "passive"))
      (node (ref "C10") (pin "2") (pinfunction "2_2") (pintype "passive"))
      (node (ref "C11") (pin "2") (pinfunction "2_2") (pintype "passive"))
      (node (ref "C12") (pin "2") (pinfunction "2_2") (pintype "passive"))
      (node (ref "C13") (pin "2") (pinfunction "2_2") (pintype "passive"))
      (node (ref "C14") (pin "2") (pinfunction "2_2") (pintype "passive"))
      (node (ref "C15") (pin "2") (pinfunction "2_2") (pintype "passive"))
      (node (ref "C16") (pin "2") (pinfunction "2_2") (pintype "passive"))
      (node (ref "C17") (pin "1") (pinfunction "1_1") (pintype "passive"))
      (node (ref "C18") (pin "1") (pinfunction "1_1") (pintype "passive"))
      (node (ref "C19") (pin "2") (pinfunction "2_2") (pintype "passive"))
      (node (ref "C2") (pin "2") (pinfunction "2_2") (pintype "passive"))
      (node (ref "C20") (pin "2") (pinfunction "2_2") (pintype "passive"))
      (node (ref "C21") (pin "2") (pinfunction "2_2") (pintype "passive"))
      (node (ref "C22") (pin "2") (pinfunction "2_2") (pintype "passive"))
      (node (ref "C23") (pin "2") (pinfunction "2_2") (pintype "passive"))
      (node (ref "C24") (pin "1") (pinfunction "1_1") (pintype "passive"))
      (node (ref "C25") (pin "2") (pinfunction "2_2") (pintype "passive"))
      (node (ref "C27") (pin "1") (pinfunction "1_1") (pintype "passive"))
      (node (ref "C29") (pin "1") (pinfunction "1_1") (pintype "passive"))
      (node (ref "C3") (pin "2") (pinfunction "2_2") (pintype "passive"))
      (node (ref "C30") (pin "1") (pinfunction "1_1") (pintype "passive"))
      (node (ref "C31") (pin "1") (pinfunction "1_1") (pintype "passive"))
      (node (ref "C32") (pin "1") (pinfunction "1_1") (pintype "passive"))
      (node (ref "C33") (pin "2") (pinfunction "2_2") (pintype "passive"))
      (node (ref "C34") (pin "1") (pinfunction "1_1") (pintype "passive"))
      (node (ref "C37") (pin "1") (pinfunction "1_1") (pintype "passive"))
      (node (ref "C38") (pin "1") (pinfunction "1_1") (pintype "passive"))
      (node (ref "C39") (pin "2") (pinfunction "2_2") (pintype "passive"))
      (node (ref "C4") (pin "2") (pinfunction "2_2") (pintype "passive"))
      (node (ref "C42") (pin "1") (pinfunction "1_1") (pintype "passive"))
      (node (ref "C43") (pin "1") (pinfunction "1_1") (pintype "passive"))
      (node (ref "C5") (pin "2") (pinfunction "2_2") (pintype "passive"))
      (node (ref "C6") (pin "2") (pinfunction "2_2") (pintype "passive"))
      (node (ref "C7") (pin "2") (pinfunction "2_2") (pintype "passive"))
      (node (ref "C8") (pin "2") (pinfunction "2_2") (pintype "passive"))
      (node (ref "C9") (pin "2") (pinfunction "2_2") (pintype "passive"))
      (node (ref "D3") (pin "2") (pinfunction "GND_2") (pintype "bidirectional"))
      (node (ref "D4") (pin "1") (pinfunction "K_1") (pintype "bidirectional"))
      (node (ref "EPD_C1") (pin "2") (pinfunction "2_2") (pintype "passive"))
      (node (ref "EPD_C10") (pin "2") (pinfunction "2_2") (pintype "passive"))
      (node (ref "EPD_C11") (pin "2") (pinfunction "2_2") (pintype "passive"))
      (node (ref "EPD_C12") (pin "2") (pinfunction "2_2") (pintype "passive"))
      (node (ref "EPD_C2") (pin "2") (pinfunction "2_2") (pintype "passive"))
      (node (ref "EPD_C5") (pin "2") (pinfunction "2_2") (pintype "passive"))
      (node (ref "EPD_C6") (pin "2") (pinfunction "2_2") (pintype "passive"))
      (node (ref "EPD_C7") (pin "2") (pinfunction "2_2") (pintype "passive"))
      (node (ref "EPD_C8") (pin "2") (pinfunction "2_2") (pintype "passive"))
      (node (ref "EPD_C9") (pin "2") (pinfunction "2_2") (pintype "passive"))
      (node (ref "IC1") (pin "D2") (pinfunction "GND_D2") (pintype "bidirectional"))
      (node (ref "IC2") (pin "B1") (pinfunction "IN/TRIG_B1") (pintype "bidirectional"))
      (node (ref "IC2") (pin "B3") (pinfunction "GND_B3") (pintype "bidirectional"))
      (node (ref "IC3") (pin "8") (pinfunction "GNDIO_8") (pintype "bidirectional"))
      (node (ref "IC3") (pin "9") (pinfunction "GND_9") (pintype "bidirectional"))
      (node (ref "IC9") (pin "B1") (pinfunction "VSEL_B1") (pintype "bidirectional"))
      (node (ref "IC9") (pin "C1") (pinfunction "AGND_C1") (pintype "bidirectional"))
      (node (ref "IC9") (pin "C2") (pinfunction "PGND_1_C2") (pintype "bidirectional"))
      (node (ref "IC9") (pin "C3") (pinfunction "PGND_2_C3") (pintype "bidirectional"))
      (node (ref "J1") (pin "17") (pinfunction "17_17") (pintype "bidirectional"))
      (node (ref "J1") (pin "8") (pinfunction "8_8") (pintype "bidirectional"))
      (node (ref "J1") (pin "MP1") (pinfunction "MP1_MP1") (pintype "bidirectional"))
      (node (ref "J1") (pin "MP2") (pinfunction "MP2_MP2") (pintype "bidirectional"))
      (node (ref "J2") (pin "3") (pinfunction "3_3") (pintype "bidirectional"))
      (node (ref "J2") (pin "5") (pinfunction "5_5") (pintype "bidirectional"))
      (node (ref "J4") (pin "A12_B1") (pinfunction "GND_A12_B1") (pintype "power_in"))
      (node (ref "J4") (pin "A1_B12") (pinfunction "GND_A1_B12") (pintype "power_in"))
      (node (ref "J4") (pin "SH1") (pinfunction "SHIELD_SH1") (pintype "passive"))
      (node (ref "J4") (pin "SH2") (pinfunction "SHIELD_SH2") (pintype "passive"))
      (node (ref "J4") (pin "SH3") (pinfunction "SHIELD_SH3") (pintype "passive"))
      (node (ref "J4") (pin "SH4") (pinfunction "SHIELD_SH4") (pintype "passive"))
      (node (ref "R1_TYPE_SEL") (pin "1") (pinfunction "1_1") (pintype "bidirectional"))
      (node (ref "R1_USB") (pin "1") (pinfunction "1_1") (pintype "bidirectional"))
      (node (ref "R2_EP_DR") (pin "1") (pinfunction "1_1") (pintype "bidirectional"))
      (node (ref "R2_USB") (pin "2") (pinfunction "2_2") (pintype "bidirectional"))
      (node (ref "R3") (pin "2") (pinfunction "2_2") (pintype "bidirectional"))
      (node (ref "R9") (pin "1") (pinfunction "1_1") (pintype "bidirectional"))
      (node (ref "SJ1") (pin "1") (pinfunction "1_1") (pintype "passive"))
      (node (ref "SW_DN") (pin "1") (pinfunction "1_1") (pintype "passive"))
      (node (ref "SW_ENT") (pin "1") (pinfunction "1_1") (pintype "passive"))
      (node (ref "SW_UP") (pin "1") (pinfunction "1_1") (pintype "passive"))
      (node (ref "TP_BAT_GND") (pin "TP") (pinfunction "TP_TP") (pintype "input"))
      (node (ref "TP_GND") (pin "TP") (pinfunction "TP_TP") (pintype "input"))
      (node (ref "U1") (pin "P$74") (pinfunction "VSS_PAD_P$74") (pintype "bidirectional"))
      (node (ref "U1") (pin "P$75") (pinfunction "VSS_PAD_P$75") (pintype "bidirectional"))
      (node (ref "U1") (pin "P$76") (pinfunction "VSS_PAD_P$76") (pintype "bidirectional"))
      (node (ref "U1") (pin "P$77") (pinfunction "VSS_PAD_P$77") (pintype "bidirectional"))
      (node (ref "U1") (pin "P$78") (pinfunction "VSS_PAD_P$78") (pintype "bidirectional"))
      (node (ref "U1") (pin "P$79") (pinfunction "VSS_PAD_P$79") (pintype "bidirectional"))
      (node (ref "U1") (pin "P$80") (pinfunction "VSS_PAD_P$80") (pintype "bidirectional"))
      (node (ref "U1") (pin "P$81") (pinfunction "VSS_PAD_P$81") (pintype "bidirectional"))
      (node (ref "U1") (pin "P$82") (pinfunction "VSS_PAD_P$82") (pintype "bidirectional"))
      (node (ref "U1") (pin "P$83") (pinfunction "VSS_PAD_P$83") (pintype "bidirectional"))
      (node (ref "U1") (pin "P$84") (pinfunction "VSS_PAD_P$84") (pintype "bidirectional"))
      (node (ref "U1") (pin "P$85") (pinfunction "VSS_PAD_P$85") (pintype "bidirectional"))
      (node (ref "U1") (pin "P$86") (pinfunction "VSS_PAD_P$86") (pintype "bidirectional"))
      (node (ref "U1") (pin "P$87") (pinfunction "VSS_PAD_P$87") (pintype "bidirectional"))
      (node (ref "U1") (pin "P$88") (pinfunction "VSS_PAD_P$88") (pintype "bidirectional"))
      (node (ref "U1") (pin "P$89") (pinfunction "VSS_PAD_P$89") (pintype "bidirectional"))
      (node (ref "U1") (pin "P$90") (pinfunction "VSS_PAD_P$90") (pintype "bidirectional"))
      (node (ref "U1") (pin "P$B7") (pinfunction "VSS_P$B7") (pintype "power_in"))
      (node (ref "U1") (pin "P$F23") (pinfunction "VSS_PA_P$F23") (pintype "bidirectional"))
      (node (ref "U3") (pin "1") (pinfunction "CTG_1") (pintype "power_in"))
      (node (ref "U3") (pin "4") (pinfunction "GND_4") (pintype "power_in"))
      (node (ref "U3") (pin "6") (pinfunction "QSTRT_6") (pintype "input"))
      (node (ref "U3") (pin "9") (pinfunction "EP_9") (pintype "power_in"))
      (node (ref "X1") (pin "2") (pinfunction "2_2") (pintype "passive"))
      (node (ref "X1") (pin "4") (pinfunction "4_4") (pintype "passive"))
    )
    (net (code "17") (name "HAPTIC_EN") (class "Default")
      (node (ref "IC2") (pin "A1") (pinfunction "EN_A1") (pintype "bidirectional"))
      (node (ref "U1") (pin "P$U1") (pinfunction "P0.12_P$U1") (pintype "bidirectional"))
    )
    (net (code "18") (name "IMU_INT1") (class "Default")
      (node (ref "IC3") (pin "5") (pinfunction "INT1_5") (pintype "bidirectional"))
      (node (ref "U1") (pin "P$N1") (pinfunction "P0.08_P$N1") (pintype "bidirectional"))
    )
    (net (code "19") (name "IMU_INT2") (class "Default")
      (node (ref "IC3") (pin "6") (pinfunction "INT2_6") (pintype "bidirectional"))
      (node (ref "U1") (pin "P$P2") (pinfunction "P1.08_P$P2") (pintype "bidirectional"))
    )
    (net (code "20") (name "LX1") (class "Default")
      (node (ref "IC9") (pin "B2") (pinfunction "SW1_1_B2") (pintype "bidirectional"))
      (node (ref "IC9") (pin "B3") (pinfunction "SW1_2_B3") (pintype "bidirectional"))
      (node (ref "L4") (pin "1") (pinfunction "1_1") (pintype "bidirectional"))
    )
    (net (code "21") (name "LX2") (class "Default")
      (node (ref "IC9") (pin "D2") (pinfunction "SW2_1_D2") (pintype "bidirectional"))
      (node (ref "IC9") (pin "D3") (pinfunction "SW2_2_D3") (pintype "bidirectional"))
      (node (ref "L4") (pin "2") (pinfunction "2_2") (pintype "bidirectional"))
    )
    (net (code "22") (name "MOSI") (class "Default")
      (node (ref "J1") (pin "14") (pinfunction "14_14") (pintype "bidirectional"))
      (node (ref "U1") (pin "P$B13") (pinfunction "P0.03/AIN1_P$B13") (pintype "bidirectional"))
    )
    (net (code "23") (name "Net-(ANT1-FEED)") (class "Default")
      (node (ref "ANT1") (pin "1") (pinfunction "FEED_1") (pintype "input"))
      (node (ref "C22") (pin "1") (pinfunction "1_1") (pintype "passive"))
      (node (ref "C4") (pin "1") (pinfunction "1_1") (pintype "passive"))
      (node (ref "L1") (pin "2") (pinfunction "2_2") (pintype "passive"))
    )
    (net (code "24") (name "Net-(D2-K)") (class "Default")
      (node (ref "C2-EP-DR") (pin "1") (pinfunction "1_1") (pintype "passive"))
      (node (ref "D2") (pin "1") (pinfunction "K_1") (pintype "bidirectional"))
      (node (ref "D4") (pin "2") (pinfunction "A_2") (pintype "bidirectional"))
    )
    (net (code "25") (name "Net-(D5-A)") (class "Default")
      (node (ref "C2-EP-DR") (pin "2") (pinfunction "2_2") (pintype "passive"))
      (node (ref "D5") (pin "2") (pinfunction "A_2") (pintype "bidirectional"))
      (node (ref "L5") (pin "1") (pinfunction "1_1") (pintype "passive"))
      (node (ref "Q3") (pin "3") (pinfunction "D_3") (pintype "bidirectional"))
    )
    (net (code "26") (name "Net-(EPD_C1-Pad1)") (class "Default")
      (node (ref "EPD_C1") (pin "1") (pinfunction "1_1") (pintype "passive"))
      (node (ref "J1") (pin "4") (pinfunction "4_4") (pintype "bidirectional"))
    )
    (net (code "27") (name "Net-(EPD_C2-Pad1)") (class "Default")
      (node (ref "EPD_C2") (pin "1") (pinfunction "1_1") (pintype "passive"))
      (node (ref "J1") (pin "5") (pinfunction "5_5") (pintype "bidirectional"))
    )
    (net (code "28") (name "Net-(EPD_C6-Pad1)") (class "Default")
      (node (ref "EPD_C6") (pin "1") (pinfunction "1_1") (pintype "passive"))
      (node (ref "J1") (pin "18") (pinfunction "18_18") (pintype "bidirectional"))
    )
    (net (code "29") (name "Net-(EPD_C7-Pad1)") (class "Default")
      (node (ref "EPD_C7") (pin "1") (pinfunction "1_1") (pintype "passive"))
      (node (ref "J1") (pin "19") (pinfunction "19_19") (pintype "bidirectional"))
    )
    (net (code "30") (name "Net-(EPD_C8-Pad1)") (class "Default")
      (node (ref "EPD_C8") (pin "1") (pinfunction "1_1") (pintype "passive"))
      (node (ref "J1") (pin "20") (pinfunction "20_20") (pintype "bidirectional"))
    )
    (net (code "31") (name "Net-(EPD_C10-Pad1)") (class "Default")
      (node (ref "EPD_C10") (pin "1") (pinfunction "1_1") (pintype "passive"))
      (node (ref "J1") (pin "22") (pinfunction "22_22") (pintype "bidirectional"))
    )
    (net (code "32") (name "Net-(EPD_C12-Pad1)") (class "Default")
      (node (ref "EPD_C12") (pin "1") (pinfunction "1_1") (pintype "passive"))
      (node (ref "J1") (pin "24") (pinfunction "24_24") (pintype "bidirectional"))
    )
    (net (code "33") (name "Net-(IC1-SYS)") (class "Default")
      (node (ref "C39") (pin "1") (pinfunction "1_1") (pintype "passive"))
      (node (ref "IC1") (pin "B2") (pinfunction "SYS_B2") (pintype "bidirectional"))
    )
    (net (code "34") (name "Net-(IC1-TS{slash}MR)") (class "Default")
      (node (ref "IC1") (pin "D1") (pinfunction "TS/MR_D1") (pintype "bidirectional"))
      (node (ref "R9") (pin "2") (pinfunction "2_2") (pintype "bidirectional"))
    )
    (net (code "35") (name "Net-(IC2-REG)") (class "Default")
      (node (ref "C32") (pin "2") (pinfunction "2_2") (pintype "passive"))
      (node (ref "IC2") (pin "A2") (pinfunction "REG_A2") (pintype "bidirectional"))
    )
    (net (code "36") (name "Net-(IC3-SDO)") (class "Default")
      (node (ref "IC3") (pin "1") (pinfunction "SDO_1") (pintype "bidirectional"))
      (node (ref "R3") (pin "1") (pinfunction "1_1") (pintype "bidirectional"))
    )
    (net (code "37") (name "Net-(IC9-SCL)") (class "Default")
      (node (ref "IC9") (pin "D1") (pinfunction "SCL_D1") (pintype "bidirectional"))
      (node (ref "R4") (pin "1") (pinfunction "1_1") (pintype "bidirectional"))
    )
    (net (code "38") (name "Net-(IC9-SDA)") (class "Default")
      (node (ref "IC9") (pin "E1") (pinfunction "SDA_E1") (pintype "bidirectional"))
      (node (ref "R2") (pin "1") (pinfunction "1_1") (pintype "bidirectional"))
    )
    (net (code "39") (name "Net-(J4-CC1)") (class "Default")
      (node (ref "J4") (pin "A5") (pinfunction "CC1_A5") (pintype "bidirectional"))
      (node (ref "R1_USB") (pin "2") (pinfunction "2_2") (pintype "bidirectional"))
    )
    (net (code "40") (name "Net-(J4-CC2)") (class "Default")
      (node (ref "J4") (pin "B5") (pinfunction "CC2_B5") (pintype "bidirectional"))
      (node (ref "R2_USB") (pin "1") (pinfunction "1_1") (pintype "bidirectional"))
    )
    (net (code "41") (name "Net-(L2-Pad2)") (class "Default")
      (node (ref "L2") (pin "2") (pinfunction "2_2") (pintype "passive"))
      (node (ref "L3") (pin "1") (pinfunction "1_1") (pintype "passive"))
    )
    (net (code "42") (name "Net-(R1_EP_DR-Pad1)") (class "Default")
      (node (ref "R1_EP_DR") (pin "1") (pinfunction "1_1") (pintype "bidirectional"))
      (node (ref "R1_TYPE_SEL") (pin "2") (pinfunction "2_2") (pintype "bidirectional"))
      (node (ref "SJ1") (pin "2") (pinfunction "2_2") (pintype "passive"))
    )
    (net (code "43") (name "Net-(U1-ANT)") (class "Default")
      (node (ref "C3") (pin "1") (pinfunction "1_1") (pintype "passive"))
      (node (ref "L1") (pin "1") (pinfunction "1_1") (pintype "passive"))
      (node (ref "U1") (pin "P$H23") (pinfunction "ANT_P$H23") (pintype "bidirectional"))
    )
    (net (code "44") (name "Net-(U1-DCC)") (class "Default")
      (node (ref "L2") (pin "1") (pinfunction "1_1") (pintype "passive"))
      (node (ref "U1") (pin "P$B3") (pinfunction "DCC_P$B3") (pintype "output"))
    )
    (net (code "45") (name "Net-(U1-DEC2)") (class "Default")
      (node (ref "C13") (pin "1") (pinfunction "1_1") (pintype "passive"))
      (node (ref "U1") (pin "P$A18") (pinfunction "DEC2_P$A18") (pintype "bidirectional"))
    )
    (net (code "46") (name "Net-(U1-DEC3V3)") (class "Default")
      (node (ref "C20") (pin "1") (pinfunction "1_1") (pintype "passive"))
      (node (ref "U1") (pin "P$AC5") (pinfunction "DEC3V3_P$AC5") (pintype "bidirectional"))
    )
    (net (code "47") (name "Net-(U1-DEC5)") (class "Default")
      (node (ref "C9") (pin "1") (pinfunction "1_1") (pintype "passive"))
      (node (ref "U1") (pin "P$N24") (pinfunction "DEC5_P$N24") (pintype "bidirectional"))
    )
    (net (code "48") (name "Net-(U1-XC1)") (class "Default")
      (node (ref "C1") (pin "1") (pinfunction "1_1") (pintype "passive"))
      (node (ref "U1") (pin "P$B24") (pinfunction "XC1_P$B24") (pintype "input"))
      (node (ref "X1") (pin "1") (pinfunction "1_1") (pintype "passive"))
    )
    (net (code "49") (name "Net-(U1-XC2)") (class "Default")
      (node (ref "C2") (pin "1") (pinfunction "1_1") (pintype "passive"))
      (node (ref "U1") (pin "P$A23") (pinfunction "XC2_P$A23") (pintype "output"))
      (node (ref "X1") (pin "3") (pinfunction "3_3") (pintype "passive"))
    )
    (net (code "50") (name "OUT+") (class "Default")
      (node (ref "IC2") (pin "A3") (pinfunction "OUT+_A3") (pintype "bidirectional"))
      (node (ref "TP_OP") (pin "TP") (pinfunction "TP_TP") (pintype "input"))
    )
    (net (code "51") (name "OUT-") (class "Default")
      (node (ref "IC2") (pin "C3") (pinfunction "OUT-_C3") (pintype "bidirectional"))
      (node (ref "TP_ON") (pin "TP") (pinfunction "TP_TP") (pintype "input"))
    )
    (net (code "52") (name "P0.00{slash}XL1") (class "Default")
      (node (ref "C17") (pin "2") (pinfunction "2_2") (pintype "passive"))
      (node (ref "U1") (pin "P$D2") (pinfunction "P0.00/XL1_P$D2") (pintype "bidirectional"))
      (node (ref "X2") (pin "2") (pinfunction "2_2") (pintype "passive"))
    )
    (net (code "53") (name "P0.00{slash}XL2") (class "Default")
      (node (ref "C18") (pin "2") (pinfunction "2_2") (pintype "passive"))
      (node (ref "X2") (pin "1") (pinfunction "1_1") (pintype "passive"))
    )
    (net (code "54") (name "P0.04") (class "Default")
      (node (ref "U1") (pin "P$J1") (pinfunction "P0.04/AIN2_P$J1") (pintype "bidirectional"))
    )
    (net (code "55") (name "P0.09") (class "Default")
      (node (ref "U1") (pin "P$L24") (pinfunction "P0.09/NFC1_P$L24") (pintype "bidirectional"))
    )
    (net (code "56") (name "P0.13") (class "Default")
      (node (ref "C30") (pin "2") (pinfunction "2_2") (pintype "passive"))
      (node (ref "R5") (pin "1") (pinfunction "1_1") (pintype "bidirectional"))
      (node (ref "SW_UP") (pin "2") (pinfunction "2_2") (pintype "passive"))
      (node (ref "U1") (pin "P$AD8") (pinfunction "P0.13_P$AD8") (pintype "bidirectional"))
    )
    (net (code "57") (name "P0.14") (class "Default")
      (node (ref "C31") (pin "2") (pinfunction "2_2") (pintype "passive"))
      (node (ref "R8") (pin "1") (pinfunction "1_1") (pintype "bidirectional"))
      (node (ref "SW_ENT") (pin "2") (pinfunction "2_2") (pintype "passive"))
      (node (ref "U1") (pin "P$AC9") (pinfunction "P0.14_P$AC9") (pintype "bidirectional"))
    )
    (net (code "58") (name "P0.19") (class "Default")
      (node (ref "U1") (pin "P$AC15") (pinfunction "P0.19_P$AC15") (pintype "bidirectional"))
    )
    (net (code "59") (name "P0.20") (class "Default")
      (node (ref "U1") (pin "P$AD16") (pinfunction "P0.20_P$AD16") (pintype "bidirectional"))
    )
    (net (code "60") (name "P0.21") (class "Default")
      (node (ref "U1") (pin "P$AC17") (pinfunction "P0.21_P$AC17") (pintype "bidirectional"))
    )
    (net (code "61") (name "P0.22") (class "Default")
      (node (ref "U1") (pin "P$AD18") (pinfunction "P0.22_P$AD18") (pintype "bidirectional"))
    )
    (net (code "62") (name "P0.23") (class "Default")
      (node (ref "U1") (pin "P$AC19") (pinfunction "P0.23_P$AC19") (pintype "bidirectional"))
    )
    (net (code "63") (name "P0.24") (class "Default")
      (node (ref "U1") (pin "P$AD20") (pinfunction "P0.24_P$AD20") (pintype "bidirectional"))
    )
    (net (code "64") (name "P0.25") (class "Default")
      (node (ref "U1") (pin "P$AC21") (pinfunction "P0.25_P$AC21") (pintype "bidirectional"))
    )
    (net (code "65") (name "P0.26") (class "Default")
      (node (ref "U1") (pin "P$G1") (pinfunction "P0.26_P$G1") (pintype "bidirectional"))
    )
    (net (code "66") (name "P0.27") (class "Default")
      (node (ref "U1") (pin "P$H2") (pinfunction "P0.27_P$H2") (pintype "bidirectional"))
    )
    (net (code "67") (name "P0.28") (class "Default")
      (node (ref "U1") (pin "P$B11") (pinfunction "P0.28/AIN4_P$B11") (pintype "bidirectional"))
    )
    (net (code "68") (name "P0.29") (class "Default")
      (node (ref "U1") (pin "P$A10") (pinfunction "P0.29/AIN5_P$A10") (pintype "bidirectional"))
    )
    (net (code "69") (name "P0.30") (class "Default")
      (node (ref "U1") (pin "P$B9") (pinfunction "P0.30/AIN6_P$B9") (pintype "bidirectional"))
    )
    (net (code "70") (name "P0.31") (class "Default")
      (node (ref "U1") (pin "P$A8") (pinfunction "P0.31/AIN7_P$A8") (pintype "bidirectional"))
    )
    (net (code "71") (name "P1.01") (class "Default")
      (node (ref "Q1") (pin "1") (pinfunction "G_1") (pintype "bidirectional"))
      (node (ref "R_PWR_EPD") (pin "1") (pinfunction "1_1") (pintype "bidirectional"))
      (node (ref "U1") (pin "P$Y23") (pinfunction "P1.01_P$Y23") (pintype "bidirectional"))
    )
    (net (code "72") (name "P1.02") (class "Default")
      (node (ref "C29") (pin "2") (pinfunction "2_2") (pintype "passive"))
      (node (ref "R7") (pin "1") (pinfunction "1_1") (pintype "bidirectional"))
      (node (ref "SW_DN") (pin "2") (pinfunction "2_2") (pintype "passive"))
      (node (ref "U1") (pin "P$W24") (pinfunction "P1.02_P$W24") (pintype "bidirectional"))
    )
    (net (code "73") (name "P1.03") (class "Default")
      (node (ref "U1") (pin "P$V23") (pinfunction "P1.03_P$V23") (pintype "bidirectional"))
    )
    (net (code "74") (name "P1.04") (class "Default")
      (node (ref "U1") (pin "P$U24") (pinfunction "P1.04_P$U24") (pintype "bidirectional"))
    )
    (net (code "75") (name "P1.05") (class "Default")
      (node (ref "U1") (pin "P$T23") (pinfunction "P1.05_P$T23") (pintype "bidirectional"))
    )
    (net (code "76") (name "P1.06") (class "Default")
      (node (ref "U1") (pin "P$R24") (pinfunction "P1.06_P$R24") (pintype "bidirectional"))
    )
    (net (code "77") (name "P1.07") (class "Default")
      (node (ref "U1") (pin "P$P23") (pinfunction "P1.07_P$P23") (pintype "bidirectional"))
    )
    (net (code "78") (name "P1.09") (class "Default")
      (node (ref "U1") (pin "P$R1") (pinfunction "P1.09_P$R1") (pintype "bidirectional"))
    )
    (net (code "79") (name "P1.10") (class "Default")
      (node (ref "U1") (pin "P$A20") (pinfunction "P1.10_P$A20") (pintype "bidirectional"))
    )
    (net (code "80") (name "P1.11") (class "Default")
      (node (ref "U1") (pin "P$B19") (pinfunction "P1.11_P$B19") (pintype "bidirectional"))
    )
    (net (code "81") (name "P1.12") (class "Default")
      (node (ref "U1") (pin "P$B17") (pinfunction "P1.12_P$B17") (pintype "bidirectional"))
    )
    (net (code "82") (name "P1.13") (class "Default")
      (node (ref "U1") (pin "P$A16") (pinfunction "P1.13_P$A16") (pintype "bidirectional"))
    )
    (net (code "83") (name "P1.14") (class "Default")
      (node (ref "U1") (pin "P$B15") (pinfunction "P1.14_P$B15") (pintype "bidirectional"))
    )
    (net (code "84") (name "P1.15") (class "Default")
      (node (ref "U1") (pin "P$A14") (pinfunction "P1.15_P$A14") (pintype "bidirectional"))
    )
    (net (code "85") (name "PMIC_INT") (class "Default")
      (node (ref "IC1") (pin "A1") (pinfunction "~{INT}_A1") (pintype "bidirectional"))
      (node (ref "U1") (pin "P$T2") (pinfunction "P0.11_P$T2") (pintype "bidirectional"))
    )
    (net (code "86") (name "PREVGH") (class "Default")
      (node (ref "D5") (pin "1") (pinfunction "K_1") (pintype "bidirectional"))
      (node (ref "EPD_C9") (pin "1") (pinfunction "1_1") (pintype "passive"))
      (node (ref "J1") (pin "21") (pinfunction "21_21") (pintype "bidirectional"))
    )
    (net (code "87") (name "PREVGL") (class "Default")
      (node (ref "D2") (pin "2") (pinfunction "A_2") (pintype "bidirectional"))
      (node (ref "EPD_C11") (pin "1") (pinfunction "1_1") (pintype "passive"))
      (node (ref "J1") (pin "23") (pinfunction "23_23") (pintype "bidirectional"))
    )
    (net (code "88") (name "RESE") (class "Default")
      (node (ref "J1") (pin "3") (pinfunction "3_3") (pintype "bidirectional"))
    )
    (net (code "89") (name "RESET") (class "Default")
      (node (ref "J2") (pin "6") (pinfunction "6_6") (pintype "bidirectional"))
      (node (ref "Q3") (pin "2") (pinfunction "S_2") (pintype "bidirectional"))
      (node (ref "R1_EP_DR") (pin "2") (pinfunction "2_2") (pintype "bidirectional"))
      (node (ref "TP_RESET") (pin "TP") (pinfunction "TP_TP") (pintype "input"))
      (node (ref "U1") (pin "P$AC13") (pinfunction "P0.18/RESET_P$AC13") (pintype "bidirectional"))
    )
    (net (code "90") (name "SCK") (class "Default")
      (node (ref "J1") (pin "13") (pinfunction "13_13") (pintype "bidirectional"))
      (node (ref "U1") (pin "P$A12") (pinfunction "P0.02/AIN0_P$A12") (pintype "bidirectional"))
    )
    (net (code "91") (name "SCL") (class "Default")
      (node (ref "IC1") (pin "B1") (pinfunction "SCL_B1") (pintype "bidirectional"))
      (node (ref "IC2") (pin "C1") (pinfunction "SCL_C1") (pintype "bidirectional"))
      (node (ref "IC3") (pin "12") (pinfunction "SCX_12") (pintype "bidirectional"))
      (node (ref "R17") (pin "2") (pinfunction "2_2") (pintype "bidirectional"))
      (node (ref "R4") (pin "2") (pinfunction "2_2") (pintype "bidirectional"))
      (node (ref "TP_SCL") (pin "TP") (pinfunction "TP_TP") (pintype "input"))
      (node (ref "U1") (pin "P$M2") (pinfunction "P0.07_P$M2") (pintype "bidirectional"))
      (node (ref "U3") (pin "7") (pinfunction "SCL_7") (pintype "input"))
    )
    (net (code "92") (name "SDA") (class "Default")
      (node (ref "IC1") (pin "C1") (pinfunction "SDA_C1") (pintype "bidirectional"))
      (node (ref "IC2") (pin "B2") (pinfunction "SDA_B2") (pintype "bidirectional"))
      (node (ref "IC3") (pin "2") (pinfunction "SDX_2") (pintype "bidirectional"))
      (node (ref "R18") (pin "2") (pinfunction "2_2") (pintype "bidirectional"))
      (node (ref "R2") (pin "2") (pinfunction "2_2") (pintype "bidirectional"))
      (node (ref "TP_SDA") (pin "TP") (pinfunction "TP_TP") (pintype "input"))
      (node (ref "U1") (pin "P$L1") (pinfunction "P0.06_P$L1") (pintype "bidirectional"))
      (node (ref "U3") (pin "8") (pinfunction "SDA_8") (pintype "bidirectional"))
    )
    (net (code "93") (name "SWDCLK") (class "Default")
      (node (ref "J2") (pin "4") (pinfunction "4_4") (pintype "bidirectional"))
      (node (ref "TP_SWDCLK") (pin "TP") (pinfunction "TP_TP") (pintype "input"))
      (node (ref "U1") (pin "P$AA24") (pinfunction "SWDCLK_P$AA24") (pintype "input"))
    )
    (net (code "94") (name "SWDIO") (class "Default")
      (node (ref "J2") (pin "2") (pinfunction "2_2") (pintype "bidirectional"))
      (node (ref "TP_SWDIO") (pin "TP") (pinfunction "TP_TP") (pintype "input"))
      (node (ref "U1") (pin "P$AC24") (pinfunction "SWDIO_P$AC24") (pintype "bidirectional"))
    )
    (net (code "95") (name "SWO") (class "Default")
      (node (ref "TP_SWO") (pin "TP") (pinfunction "TP_TP") (pintype "input"))
      (node (ref "U1") (pin "P$AD22") (pinfunction "P1.00_P$AD22") (pintype "bidirectional"))
    )
    (net (code "96") (name "VBAT") (class "Default")
      (node (ref "C27") (pin "2") (pinfunction "2_2") (pintype "passive"))
      (node (ref "C37") (pin "2") (pinfunction "2_2") (pintype "passive"))
      (node (ref "IC1") (pin "C2") (pinfunction "BAT_C2") (pintype "bidirectional"))
      (node (ref "TP_VBAT") (pin "TP") (pinfunction "TP_TP") (pintype "input"))
      (node (ref "U3") (pin "2") (pinfunction "CELL_2") (pintype "power_in"))
      (node (ref "U3") (pin "3") (pinfunction "VDD_3") (pintype "power_in"))
    )
    (net (code "97") (name "VBUS") (class "Default")
      (node (ref "C21") (pin "1") (pinfunction "1_1") (pintype "passive"))
      (node (ref "C38") (pin "2") (pinfunction "2_2") (pintype "passive"))
      (node (ref "C42") (pin "2") (pinfunction "2_2") (pintype "passive"))
      (node (ref "C43") (pin "2") (pinfunction "2_2") (pintype "passive"))
      (node (ref "D3") (pin "5") (pinfunction "VBUS_5") (pintype "bidirectional"))
      (node (ref "IC1") (pin "A2") (pinfunction "IN_A2") (pintype "bidirectional"))
      (node (ref "J4") (pin "A4_B9") (pinfunction "VBUS_A4_B9") (pintype "power_in"))
      (node (ref "J4") (pin "A9_B4") (pinfunction "VBUS_A9_B4") (pintype "power_in"))
      (node (ref "U1") (pin "P$AD2") (pinfunction "VBUS_P$AD2") (pintype "power_in"))
    )
    (net (code "98") (name "VREG") (class "Default")
      (node (ref "C23") (pin "1") (pinfunction "1_1") (pintype "passive"))
      (node (ref "C24") (pin "2") (pinfunction "2_2") (pintype "passive"))
      (node (ref "IC9") (pin "A1") (pinfunction "EN_A1") (pintype "bidirectional"))
      (node (ref "IC9") (pin "A2") (pinfunction "VIN_1_A2") (pintype "bidirectional"))
      (node (ref "IC9") (pin "A3") (pinfunction "VIN_2_A3") (pintype "bidirectional"))
      (node (ref "TP_VREG") (pin "TP") (pinfunction "TP_TP") (pintype "input"))
    )
    (net (code "99") (name "unconnected-(ANT1-NC-Pad2)") (class "Default")
      (node (ref "ANT1") (pin "2") (pinfunction "NC_2") (pintype "no_connect"))
    )
    (net (code "100") (name "unconnected-(IC3-ASCL-Pad11)") (class "Default")
      (node (ref "IC3") (pin "11") (pinfunction "ASCL_11") (pintype "bidirectional"))
    )
    (net (code "101") (name "unconnected-(IC3-ASDA-Pad4)") (class "Default")
      (node (ref "IC3") (pin "4") (pinfunction "ASDA_4") (pintype "bidirectional"))
    )
    (net (code "102") (name "unconnected-(J1-Pad1)") (class "Default")
      (node (ref "J1") (pin "1") (pinfunction "1_1") (pintype "bidirectional"))
    )
    (net (code "103") (name "unconnected-(J1-Pad6)") (class "Default")
      (node (ref "J1") (pin "6") (pinfunction "6_6") (pintype "bidirectional"))
    )
    (net (code "104") (name "unconnected-(J1-Pad7)") (class "Default")
      (node (ref "J1") (pin "7") (pinfunction "7_7") (pintype "bidirectional"))
    )
    (net (code "105") (name "unconnected-(J4-SBU1-PadA8)") (class "Default")
      (node (ref "J4") (pin "A8") (pinfunction "SBU1_A8") (pintype "bidirectional"))
    )
    (net (code "106") (name "unconnected-(J4-SBU2-PadB8)") (class "Default")
      (node (ref "J4") (pin "B8") (pinfunction "SBU2_B8") (pintype "bidirectional"))
    )
    (net (code "107") (name "unconnected-(U1-DCCH-PadP$AB2)") (class "Default")
      (node (ref "U1") (pin "P$AB2") (pinfunction "DCCH_P$AB2") (pintype "bidirectional"))
    )
    (net (code "108") (name "unconnected-(U1-P0.01{slash}XL2-PadP$F2)") (class "Default")
      (node (ref "U1") (pin "P$F2") (pinfunction "P0.01/XL2_P$F2") (pintype "bidirectional"))
    )
    (net (code "109") (name "unconnected-(U1-VDDH-PadP$Y2)") (class "Default")
      (node (ref "U1") (pin "P$Y2") (pinfunction "VDDH_P$Y2") (pintype "power_in"))
    )
  )
)
